# DZ_Scheme.net
KiCad netlist of a schematic drawn in Altium Designer
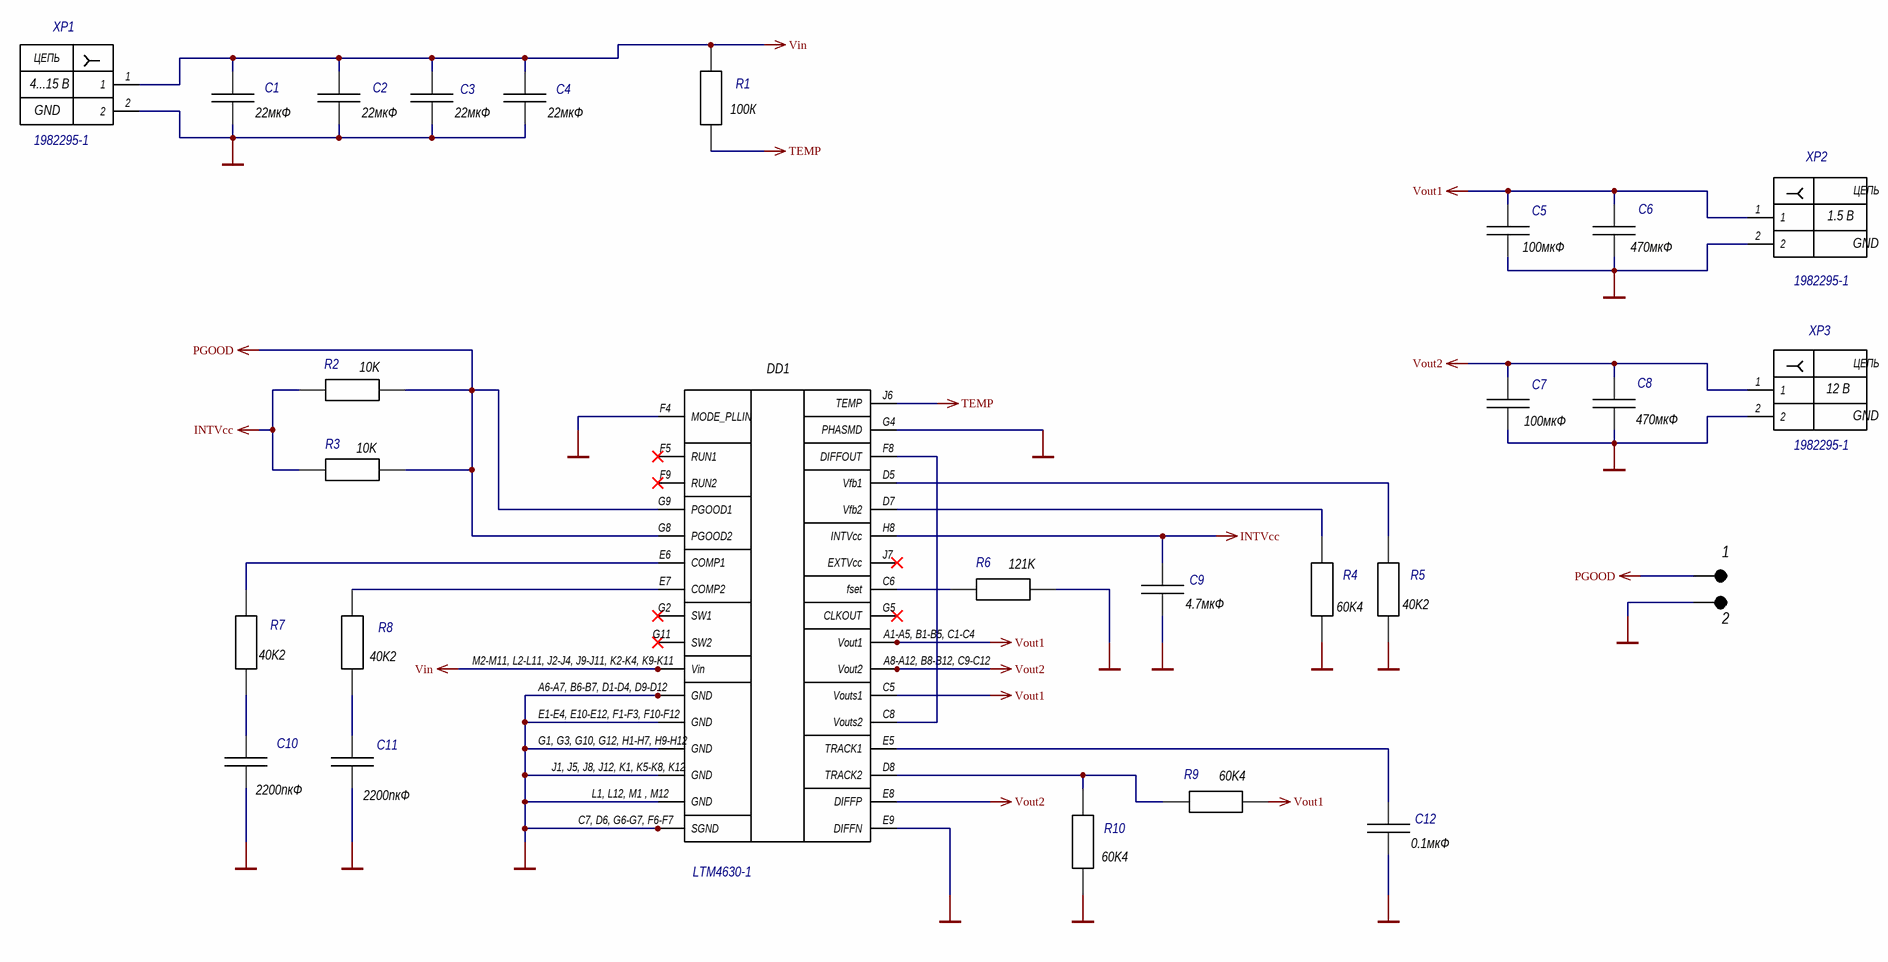
[diagram p0: DZ_Scheme.SchDoc]

(export (version "E")
  (design (tool "Eeschema 10.0.6"))
  (components
    (comp (ref "*")
      (value "TEST_PINS")
      (footprint "TEST_ZONE")
      (libsource (lib "DZ_Schlib") (part "TEST_PINS"))
    )
    (comp (ref "C1")
      (value "Capasitor")
      (footprint "CAP: 0805")
      (fields
        (field (name "PARAMETER 1") "22мкФ")
        (field (name "MANUFACTURER_PART_NUMBER") "CC0805MKX5R8BB226")
      )
      (libsource (lib "DZ_Schlib") (part "Capasitor"))
    )
    (comp (ref "C2")
      (value "Capasitor")
      (footprint "CAP: 0805")
      (fields
        (field (name "PARAMETER 1") "22мкФ")
        (field (name "MANUFACTURER_PART_NUMBER") "CC0805MKX5R8BB226")
      )
      (libsource (lib "DZ_Schlib") (part "Capasitor"))
    )
    (comp (ref "C3")
      (value "Capasitor")
      (footprint "CAP: 0805")
      (fields
        (field (name "PARAMETER 1") "22мкФ")
        (field (name "MANUFACTURER_PART_NUMBER") "CC0805MKX5R8BB226")
      )
      (libsource (lib "DZ_Schlib") (part "Capasitor"))
    )
    (comp (ref "C4")
      (value "Capasitor")
      (footprint "CAP: 0805")
      (fields
        (field (name "PARAMETER 1") "22мкФ")
        (field (name "MANUFACTURER_PART_NUMBER") "CC0805MKX5R8BB226")
      )
      (libsource (lib "DZ_Schlib") (part "Capasitor"))
    )
    (comp (ref "C5")
      (value "Capasitor")
      (footprint "CAP: 0805")
      (fields
        (field (name "PARAMETER 1") "100мкФ")
        (field (name "MANUFACTURER_PART_NUMBER") "GRM21BR60J107ME15")
      )
      (libsource (lib "DZ_Schlib") (part "Capasitor"))
    )
    (comp (ref "C6")
      (value "Capasitor")
      (footprint "CAP: 0805")
      (fields
        (field (name "PARAMETER 1") "470мкФ")
        (field (name "MANUFACTURER_PART_NUMBER") "CC0805KKX7R7BB474")
      )
      (libsource (lib "DZ_Schlib") (part "Capasitor"))
    )
    (comp (ref "C7")
      (value "Capasitor")
      (footprint "CAP: 0805")
      (fields
        (field (name "PARAMETER 1") "100мкФ")
        (field (name "MANUFACTURER_PART_NUMBER") "GRM21BR60J107ME15")
      )
      (libsource (lib "DZ_Schlib") (part "Capasitor"))
    )
    (comp (ref "C8")
      (value "Capasitor")
      (footprint "CAP: 0805")
      (fields
        (field (name "PARAMETER 1") "470мкФ")
        (field (name "MANUFACTURER_PART_NUMBER") "CC0805KKX7R7BB474")
      )
      (libsource (lib "DZ_Schlib") (part "Capasitor"))
    )
    (comp (ref "C9")
      (value "Capasitor")
      (footprint "CAP: 0805")
      (fields
        (field (name "PARAMETER 1") "4.7мкФ")
        (field (name "MANUFACTURER_PART_NUMBER") "CC0805KKX5R8BB475")
      )
      (libsource (lib "DZ_Schlib") (part "Capasitor"))
    )
    (comp (ref "C10")
      (value "Capasitor")
      (footprint "CAP: 0805")
      (fields
        (field (name "PARAMETER 1") "2200пкФ")
        (field (name "MANUFACTURER_PART_NUMBER") "CC0805JKNPO9BN222")
      )
      (libsource (lib "DZ_Schlib") (part "Capasitor"))
    )
    (comp (ref "C11")
      (value "Capasitor")
      (footprint "CAP: 0805")
      (fields
        (field (name "PARAMETER 1") "2200пкФ")
        (field (name "MANUFACTURER_PART_NUMBER") "CC0805JKNPO9BN222")
      )
      (libsource (lib "DZ_Schlib") (part "Capasitor"))
    )
    (comp (ref "C12")
      (value "Capasitor")
      (footprint "CAP: 0805")
      (fields
        (field (name "PARAMETER 1") "0.1мкФ")
        (field (name "MANUFACTURER_PART_NUMBER") "CC0805JRX7R8BB104")
      )
      (libsource (lib "DZ_Schlib") (part "Capasitor"))
    )
    (comp (ref "DD1")
      (value "LTM4630-1")
      (footprint "BGA144C127P12X12_1600X1600X501")
      (libsource (lib "DZ_Schlib") (part "LTM4630-1"))
    )
    (comp (ref "R1")
      (value "Resistor")
      (footprint "RES: 1206")
      (fields
        (field (name "PARAMETER 1") "100К")
        (field (name "MANUFACTURER_PART_NUMBER") "CRCW1206100KFKEA")
      )
      (libsource (lib "DZ_Schlib") (part "Resistor"))
    )
    (comp (ref "R2")
      (value "Resistor")
      (footprint "RES: 1206")
      (fields (field (name "PARAMETER 1") "10K") (field (name "MANUFACTURER_PART_NUMBER") "CRCW120610K0FKEA"))
      (libsource (lib "DZ_Schlib") (part "Resistor"))
    )
    (comp (ref "R3")
      (value "Resistor")
      (footprint "RES: 1206")
      (fields (field (name "PARAMETER 1") "10K") (field (name "MANUFACTURER_PART_NUMBER") "CRCW120610K0FKEA"))
      (libsource (lib "DZ_Schlib") (part "Resistor"))
    )
    (comp (ref "R4")
      (value "Resistor")
      (footprint "RES: 1206")
      (fields
        (field (name "PARAMETER 1") "60K4")
        (field (name "MANUFACTURER_PART_NUMBER") "CRCW120660K4FKEA")
      )
      (libsource (lib "DZ_Schlib") (part "Resistor"))
    )
    (comp (ref "R5")
      (value "Resistor")
      (footprint "RES: 1206")
      (fields
        (field (name "PARAMETER 1") "40K2")
        (field (name "MANUFACTURER_PART_NUMBER") "CRCW120640K2FHEAP")
      )
      (libsource (lib "DZ_Schlib") (part "Resistor"))
    )
    (comp (ref "R6")
      (value "Resistor")
      (footprint "RES: 1206")
      (fields
        (field (name "PARAMETER 1") "121K")
        (field (name "MANUFACTURER_PART_NUMBER") "CRCW1206121KFHEAP")
      )
      (libsource (lib "DZ_Schlib") (part "Resistor"))
    )
    (comp (ref "R7")
      (value "Resistor")
      (footprint "RES: 1206")
      (fields
        (field (name "PARAMETER 1") "40K2")
        (field (name "MANUFACTURER_PART_NUMBER") "CRCW120640K2FHEAP")
      )
      (libsource (lib "DZ_Schlib") (part "Resistor"))
    )
    (comp (ref "R8")
      (value "Resistor")
      (footprint "RES: 1206")
      (fields
        (field (name "PARAMETER 1") "40K2")
        (field (name "MANUFACTURER_PART_NUMBER") "CRCW120640K2FHEAP")
      )
      (libsource (lib "DZ_Schlib") (part "Resistor"))
    )
    (comp (ref "R9")
      (value "Resistor")
      (footprint "RES: 1206")
      (fields
        (field (name "PARAMETER 1") "60K4")
        (field (name "MANUFACTURER_PART_NUMBER") "CRCW120660K4FKEA")
      )
      (libsource (lib "DZ_Schlib") (part "Resistor"))
    )
    (comp (ref "R10")
      (value "Resistor")
      (footprint "RES: 1206")
      (fields
        (field (name "PARAMETER 1") "60K4")
        (field (name "MANUFACTURER_PART_NUMBER") "CRCW120660K4FKEA")
      )
      (libsource (lib "DZ_Schlib") (part "Resistor"))
    )
    (comp (ref "XP1")
      (value "1982295-1")
      (footprint "DZ_PcbLib:19822951")
      (description "Connector")
      (fields (field (name "MOUSER PART NUMBER") "571-1982295-1"))
      (libsource (lib "") (part "1982295-1_1"))
    )
    (comp (ref "XP2")
      (value "1982295-1")
      (footprint "DZ_PcbLib:19822951")
      (description "Connector")
      (fields (field (name "MOUSER PART NUMBER") "571-1982295-1"))
      (libsource (lib "DZ_Schlib") (part "1982295-1"))
    )
    (comp (ref "XP3")
      (value "1982295-1")
      (footprint "DZ_PcbLib:19822951")
      (description "Connector")
      (fields (field (name "MOUSER PART NUMBER") "571-1982295-1"))
      (libsource (lib "DZ_Schlib") (part "1982295-1"))
    )
  )
  (nets
    (net (code "1") (name "GND") (class "Default")
      (node (ref "*") (pin "2") (pinfunction "2_2") (pintype "passive"))
      (node (ref "C1") (pin "1") (pinfunction "1_1") (pintype "passive"))
      (node (ref "C10") (pin "1") (pinfunction "1_1") (pintype "passive"))
      (node (ref "C11") (pin "2") (pinfunction "2_2") (pintype "passive"))
      (node (ref "C12") (pin "1") (pinfunction "1_1") (pintype "passive"))
      (node (ref "C2") (pin "1") (pinfunction "1_1") (pintype "passive"))
      (node (ref "C3") (pin "1") (pinfunction "1_1") (pintype "passive"))
      (node (ref "C4") (pin "1") (pinfunction "1_1") (pintype "passive"))
      (node (ref "C5") (pin "1") (pinfunction "1_1") (pintype "passive"))
      (node (ref "C6") (pin "2") (pinfunction "2_2") (pintype "passive"))
      (node (ref "C7") (pin "1") (pinfunction "1_1") (pintype "passive"))
      (node (ref "C8") (pin "2") (pinfunction "2_2") (pintype "passive"))
      (node (ref "C9") (pin "1") (pinfunction "1_1") (pintype "passive"))
      (node (ref "DD1") (pin "A6") (pinfunction "GND_A6") (pintype "open_emitter"))
      (node (ref "DD1") (pin "A7") (pinfunction "GND_A7") (pintype "open_emitter"))
      (node (ref "DD1") (pin "B6") (pinfunction "GND_B6") (pintype "open_emitter"))
      (node (ref "DD1") (pin "B7") (pinfunction "GND_B7") (pintype "open_emitter"))
      (node (ref "DD1") (pin "C7") (pinfunction "SGND_C7") (pintype "open_emitter"))
      (node (ref "DD1") (pin "D1") (pinfunction "GND_D1") (pintype "open_emitter"))
      (node (ref "DD1") (pin "D10") (pinfunction "GND_D10") (pintype "open_emitter"))
      (node (ref "DD1") (pin "D11") (pinfunction "GND_D11") (pintype "open_emitter"))
      (node (ref "DD1") (pin "D12") (pinfunction "GND_D12") (pintype "open_emitter"))
      (node (ref "DD1") (pin "D2") (pinfunction "GND_D2") (pintype "open_emitter"))
      (node (ref "DD1") (pin "D3") (pinfunction "GND_D3") (pintype "open_emitter"))
      (node (ref "DD1") (pin "D4") (pinfunction "GND_D4") (pintype "open_emitter"))
      (node (ref "DD1") (pin "D6") (pinfunction "SGND_D6") (pintype "open_emitter"))
      (node (ref "DD1") (pin "D9") (pinfunction "GND_D9") (pintype "open_emitter"))
      (node (ref "DD1") (pin "E1") (pinfunction "GND_E1") (pintype "open_emitter"))
      (node (ref "DD1") (pin "E10") (pinfunction "GND_E10") (pintype "open_emitter"))
      (node (ref "DD1") (pin "E11") (pinfunction "GND_E11") (pintype "open_emitter"))
      (node (ref "DD1") (pin "E12") (pinfunction "GND_E12") (pintype "open_emitter"))
      (node (ref "DD1") (pin "E2") (pinfunction "GND_E2") (pintype "open_emitter"))
      (node (ref "DD1") (pin "E3") (pinfunction "GND_E3") (pintype "open_emitter"))
      (node (ref "DD1") (pin "E4") (pinfunction "GND_E4") (pintype "open_emitter"))
      (node (ref "DD1") (pin "E9") (pinfunction "DIFFN_E9") (pintype "open_emitter"))
      (node (ref "DD1") (pin "F1") (pinfunction "GND_F1") (pintype "open_emitter"))
      (node (ref "DD1") (pin "F10") (pinfunction "GND_F10") (pintype "open_emitter"))
      (node (ref "DD1") (pin "F11") (pinfunction "GND_F11") (pintype "open_emitter"))
      (node (ref "DD1") (pin "F12") (pinfunction "GND_F12") (pintype "open_emitter"))
      (node (ref "DD1") (pin "F2") (pinfunction "GND_F2") (pintype "open_emitter"))
      (node (ref "DD1") (pin "F3") (pinfunction "GND_F3") (pintype "open_emitter"))
      (node (ref "DD1") (pin "F4") (pinfunction "MODE_PLLIN_F4") (pintype "open_emitter"))
      (node (ref "DD1") (pin "F6") (pinfunction "SGND_F6") (pintype "open_emitter"))
      (node (ref "DD1") (pin "F7") (pinfunction "SGND_F7") (pintype "open_emitter"))
      (node (ref "DD1") (pin "G1") (pinfunction "GND_G1") (pintype "open_emitter"))
      (node (ref "DD1") (pin "G10") (pinfunction "GND_G10") (pintype "open_emitter"))
      (node (ref "DD1") (pin "G12") (pinfunction "GND_G12") (pintype "open_emitter"))
      (node (ref "DD1") (pin "G3") (pinfunction "GND_G3") (pintype "open_emitter"))
      (node (ref "DD1") (pin "G4") (pinfunction "PHASMD_G4") (pintype "open_emitter"))
      (node (ref "DD1") (pin "G6") (pinfunction "SGND_G6") (pintype "open_emitter"))
      (node (ref "DD1") (pin "G7") (pinfunction "SGND_G7") (pintype "open_emitter"))
      (node (ref "DD1") (pin "H1") (pinfunction "GND_H1") (pintype "open_emitter"))
      (node (ref "DD1") (pin "H10") (pinfunction "GND_H10") (pintype "open_emitter"))
      (node (ref "DD1") (pin "H11") (pinfunction "GND_H11") (pintype "open_emitter"))
      (node (ref "DD1") (pin "H12") (pinfunction "GND_H12") (pintype "open_emitter"))
      (node (ref "DD1") (pin "H2") (pinfunction "GND_H2") (pintype "open_emitter"))
      (node (ref "DD1") (pin "H3") (pinfunction "GND_H3") (pintype "open_emitter"))
      (node (ref "DD1") (pin "H4") (pinfunction "GND_H4") (pintype "open_emitter"))
      (node (ref "DD1") (pin "H5") (pinfunction "GND_H5") (pintype "open_emitter"))
      (node (ref "DD1") (pin "H6") (pinfunction "GND_H6") (pintype "open_emitter"))
      (node (ref "DD1") (pin "H7") (pinfunction "GND_H7") (pintype "open_emitter"))
      (node (ref "DD1") (pin "H9") (pinfunction "GND_H9") (pintype "open_emitter"))
      (node (ref "DD1") (pin "J1") (pinfunction "GND_J1") (pintype "open_emitter"))
      (node (ref "DD1") (pin "J12") (pinfunction "GND_J12") (pintype "open_emitter"))
      (node (ref "DD1") (pin "J5") (pinfunction "GND_J5") (pintype "open_emitter"))
      (node (ref "DD1") (pin "J8") (pinfunction "GND_J8") (pintype "open_emitter"))
      (node (ref "DD1") (pin "K1") (pinfunction "GND_K1") (pintype "open_emitter"))
      (node (ref "DD1") (pin "K12") (pinfunction "GND_K12") (pintype "open_emitter"))
      (node (ref "DD1") (pin "K5") (pinfunction "GND_K5") (pintype "open_emitter"))
      (node (ref "DD1") (pin "K6") (pinfunction "GND_K6") (pintype "open_emitter"))
      (node (ref "DD1") (pin "K7") (pinfunction "GND_K7") (pintype "open_emitter"))
      (node (ref "DD1") (pin "K8") (pinfunction "GND_K8") (pintype "open_emitter"))
      (node (ref "DD1") (pin "L1") (pinfunction "GND_L1") (pintype "open_emitter"))
      (node (ref "DD1") (pin "L12") (pinfunction "GND_L12") (pintype "open_emitter"))
      (node (ref "DD1") (pin "M1") (pinfunction "GND_M1") (pintype "open_emitter"))
      (node (ref "DD1") (pin "M12") (pinfunction "GND_M12") (pintype "open_emitter"))
      (node (ref "R10") (pin "1") (pinfunction "1_1") (pintype "passive"))
      (node (ref "R4") (pin "1") (pinfunction "1_1") (pintype "passive"))
      (node (ref "R5") (pin "1") (pinfunction "1_1") (pintype "passive"))
      (node (ref "R6") (pin "2") (pinfunction "2_2") (pintype "passive"))
      (node (ref "XP1") (pin "2") (pinfunction "2_2") (pintype "open_emitter"))
      (node (ref "XP2") (pin "2") (pinfunction "2_2") (pintype "open_emitter"))
      (node (ref "XP3") (pin "2") (pinfunction "2_2") (pintype "open_emitter"))
    )
    (net (code "2") (name "INTVcc") (class "Default")
      (node (ref "C9") (pin "2") (pinfunction "2_2") (pintype "passive"))
      (node (ref "DD1") (pin "H8") (pinfunction "INTVcc_H8") (pintype "open_emitter"))
      (node (ref "R2") (pin "1") (pinfunction "1_1") (pintype "passive"))
      (node (ref "R3") (pin "1") (pinfunction "1_1") (pintype "passive"))
    )
    (net (code "3") (name "Net-(C10-Pad2)") (class "Default")
      (node (ref "C10") (pin "2") (pinfunction "2_2") (pintype "passive"))
      (node (ref "R7") (pin "2") (pinfunction "2_2") (pintype "passive"))
    )
    (net (code "4") (name "Net-(C11-Pad1)") (class "Default")
      (node (ref "C11") (pin "1") (pinfunction "1_1") (pintype "passive"))
      (node (ref "R8") (pin "2") (pinfunction "2_2") (pintype "passive"))
    )
    (net (code "5") (name "Net-(DD1-COMP1)") (class "Default")
      (node (ref "DD1") (pin "E6") (pinfunction "COMP1_E6") (pintype "open_emitter"))
      (node (ref "R7") (pin "1") (pinfunction "1_1") (pintype "passive"))
    )
    (net (code "6") (name "Net-(DD1-COMP2)") (class "Default")
      (node (ref "DD1") (pin "E7") (pinfunction "COMP2_E7") (pintype "open_emitter"))
      (node (ref "R8") (pin "1") (pinfunction "1_1") (pintype "passive"))
    )
    (net (code "7") (name "Net-(DD1-DIFFOUT)") (class "Default")
      (node (ref "DD1") (pin "C8") (pinfunction "Vouts2_C8") (pintype "open_emitter"))
      (node (ref "DD1") (pin "F8") (pinfunction "DIFFOUT_F8") (pintype "open_emitter"))
    )
    (net (code "8") (name "Net-(DD1-TRACK1)") (class "Default")
      (node (ref "C12") (pin "2") (pinfunction "2_2") (pintype "passive"))
      (node (ref "DD1") (pin "E5") (pinfunction "TRACK1_E5") (pintype "open_emitter"))
    )
    (net (code "9") (name "Net-(DD1-TRACK2)") (class "Default")
      (node (ref "DD1") (pin "D8") (pinfunction "TRACK2_D8") (pintype "open_emitter"))
      (node (ref "R10") (pin "2") (pinfunction "2_2") (pintype "passive"))
      (node (ref "R9") (pin "2") (pinfunction "2_2") (pintype "passive"))
    )
    (net (code "10") (name "Net-(DD1-Vfb1)") (class "Default")
      (node (ref "DD1") (pin "D5") (pinfunction "Vfb1_D5") (pintype "open_emitter"))
      (node (ref "R5") (pin "2") (pinfunction "2_2") (pintype "passive"))
    )
    (net (code "11") (name "Net-(DD1-Vfb2)") (class "Default")
      (node (ref "DD1") (pin "D7") (pinfunction "Vfb2_D7") (pintype "open_emitter"))
      (node (ref "R4") (pin "2") (pinfunction "2_2") (pintype "passive"))
    )
    (net (code "12") (name "Net-(DD1-fset)") (class "Default")
      (node (ref "DD1") (pin "C6") (pinfunction "fset_C6") (pintype "open_emitter"))
      (node (ref "R6") (pin "1") (pinfunction "1_1") (pintype "passive"))
    )
    (net (code "13") (name "PGOOD") (class "Default")
      (node (ref "*") (pin "1") (pinfunction "1_1") (pintype "passive"))
      (node (ref "DD1") (pin "G8") (pinfunction "PGOOD2_G8") (pintype "open_emitter"))
      (node (ref "DD1") (pin "G9") (pinfunction "PGOOD1_G9") (pintype "open_emitter"))
      (node (ref "R2") (pin "2") (pinfunction "2_2") (pintype "passive"))
      (node (ref "R3") (pin "2") (pinfunction "2_2") (pintype "passive"))
    )
    (net (code "14") (name "TEMP") (class "Default")
      (node (ref "DD1") (pin "J6") (pinfunction "TEMP_J6") (pintype "open_emitter"))
      (node (ref "R1") (pin "1") (pinfunction "1_1") (pintype "passive"))
    )
    (net (code "15") (name "Vin") (class "Default")
      (node (ref "C1") (pin "2") (pinfunction "2_2") (pintype "passive"))
      (node (ref "C2") (pin "2") (pinfunction "2_2") (pintype "passive"))
      (node (ref "C3") (pin "2") (pinfunction "2_2") (pintype "passive"))
      (node (ref "C4") (pin "2") (pinfunction "2_2") (pintype "passive"))
      (node (ref "DD1") (pin "J10") (pinfunction "Vin_J10") (pintype "open_emitter"))
      (node (ref "DD1") (pin "J11") (pinfunction "Vin_J11") (pintype "open_emitter"))
      (node (ref "DD1") (pin "J2") (pinfunction "Vin_J2") (pintype "open_emitter"))
      (node (ref "DD1") (pin "J3") (pinfunction "Vin_J3") (pintype "open_emitter"))
      (node (ref "DD1") (pin "J4") (pinfunction "Vin_J4") (pintype "open_emitter"))
      (node (ref "DD1") (pin "J9") (pinfunction "Vin_J9") (pintype "open_emitter"))
      (node (ref "DD1") (pin "K10") (pinfunction "Vin_K10") (pintype "open_emitter"))
      (node (ref "DD1") (pin "K11") (pinfunction "Vin_K11") (pintype "open_emitter"))
      (node (ref "DD1") (pin "K2") (pinfunction "Vin_K2") (pintype "open_emitter"))
      (node (ref "DD1") (pin "K3") (pinfunction "Vin_K3") (pintype "open_emitter"))
      (node (ref "DD1") (pin "K4") (pinfunction "Vin_K4") (pintype "open_emitter"))
      (node (ref "DD1") (pin "K9") (pinfunction "Vin_K9") (pintype "open_emitter"))
      (node (ref "DD1") (pin "L10") (pinfunction "Vin_L10") (pintype "open_emitter"))
      (node (ref "DD1") (pin "L11") (pinfunction "Vin_L11") (pintype "open_emitter"))
      (node (ref "DD1") (pin "L2") (pinfunction "Vin_L2") (pintype "open_emitter"))
      (node (ref "DD1") (pin "L3") (pinfunction "Vin_L3") (pintype "open_emitter"))
      (node (ref "DD1") (pin "L4") (pinfunction "Vin_L4") (pintype "open_emitter"))
      (node (ref "DD1") (pin "L5") (pinfunction "Vin_L5") (pintype "open_emitter"))
      (node (ref "DD1") (pin "L6") (pinfunction "Vin_L6") (pintype "open_emitter"))
      (node (ref "DD1") (pin "L7") (pinfunction "Vin_L7") (pintype "open_emitter"))
      (node (ref "DD1") (pin "L8") (pinfunction "Vin_L8") (pintype "open_emitter"))
      (node (ref "DD1") (pin "L9") (pinfunction "Vin_L9") (pintype "open_emitter"))
      (node (ref "DD1") (pin "M10") (pinfunction "Vin_M10") (pintype "open_emitter"))
      (node (ref "DD1") (pin "M11") (pinfunction "Vin_M11") (pintype "open_emitter"))
      (node (ref "DD1") (pin "M2") (pinfunction "Vin_M2") (pintype "open_emitter"))
      (node (ref "DD1") (pin "M3") (pinfunction "Vin_M3") (pintype "open_emitter"))
      (node (ref "DD1") (pin "M4") (pinfunction "Vin_M4") (pintype "open_emitter"))
      (node (ref "DD1") (pin "M5") (pinfunction "Vin_M5") (pintype "open_emitter"))
      (node (ref "DD1") (pin "M6") (pinfunction "Vin_M6") (pintype "open_emitter"))
      (node (ref "DD1") (pin "M7") (pinfunction "Vin_M7") (pintype "open_emitter"))
      (node (ref "DD1") (pin "M8") (pinfunction "Vin_M8") (pintype "open_emitter"))
      (node (ref "DD1") (pin "M9") (pinfunction "Vin_M9") (pintype "open_emitter"))
      (node (ref "R1") (pin "2") (pinfunction "2_2") (pintype "passive"))
      (node (ref "XP1") (pin "1") (pinfunction "1_1") (pintype "passive"))
    )
    (net (code "16") (name "Vout1") (class "Default")
      (node (ref "C5") (pin "2") (pinfunction "2_2") (pintype "passive"))
      (node (ref "C6") (pin "1") (pinfunction "1_1") (pintype "passive"))
      (node (ref "DD1") (pin "A1") (pinfunction "Vout1_A1") (pintype "open_emitter"))
      (node (ref "DD1") (pin "A2") (pinfunction "Vout1_A2") (pintype "open_emitter"))
      (node (ref "DD1") (pin "A3") (pinfunction "Vout1_A3") (pintype "open_emitter"))
      (node (ref "DD1") (pin "A4") (pinfunction "Vout1_A4") (pintype "open_emitter"))
      (node (ref "DD1") (pin "A5") (pinfunction "Vout1_A5") (pintype "open_emitter"))
      (node (ref "DD1") (pin "B1") (pinfunction "Vout1_B1") (pintype "open_emitter"))
      (node (ref "DD1") (pin "B2") (pinfunction "Vout1_B2") (pintype "open_emitter"))
      (node (ref "DD1") (pin "B3") (pinfunction "Vout1_B3") (pintype "open_emitter"))
      (node (ref "DD1") (pin "B4") (pinfunction "Vout1_B4") (pintype "open_emitter"))
      (node (ref "DD1") (pin "B5") (pinfunction "Vout1_B5") (pintype "open_emitter"))
      (node (ref "DD1") (pin "C1") (pinfunction "Vout1_C1") (pintype "open_emitter"))
      (node (ref "DD1") (pin "C2") (pinfunction "Vout1_C2") (pintype "open_emitter"))
      (node (ref "DD1") (pin "C3") (pinfunction "Vout1_C3") (pintype "open_emitter"))
      (node (ref "DD1") (pin "C4") (pinfunction "Vout1_C4") (pintype "open_emitter"))
      (node (ref "DD1") (pin "C5") (pinfunction "Vouts1_C5") (pintype "open_emitter"))
      (node (ref "R9") (pin "1") (pinfunction "1_1") (pintype "passive"))
      (node (ref "XP2") (pin "1") (pinfunction "1_1") (pintype "passive"))
    )
    (net (code "17") (name "Vout2") (class "Default")
      (node (ref "C7") (pin "2") (pinfunction "2_2") (pintype "passive"))
      (node (ref "C8") (pin "1") (pinfunction "1_1") (pintype "passive"))
      (node (ref "DD1") (pin "A10") (pinfunction "Vout2_A10") (pintype "open_emitter"))
      (node (ref "DD1") (pin "A11") (pinfunction "Vout2_A11") (pintype "open_emitter"))
      (node (ref "DD1") (pin "A12") (pinfunction "Vout2_A12") (pintype "open_emitter"))
      (node (ref "DD1") (pin "A8") (pinfunction "Vout2_A8") (pintype "open_emitter"))
      (node (ref "DD1") (pin "A9") (pinfunction "Vout2_A9") (pintype "open_emitter"))
      (node (ref "DD1") (pin "B10") (pinfunction "Vout2_B10") (pintype "open_emitter"))
      (node (ref "DD1") (pin "B11") (pinfunction "Vout2_B11") (pintype "open_emitter"))
      (node (ref "DD1") (pin "B12") (pinfunction "Vout2_B12") (pintype "open_emitter"))
      (node (ref "DD1") (pin "B8") (pinfunction "Vout2_B8") (pintype "open_emitter"))
      (node (ref "DD1") (pin "B9") (pinfunction "Vout2_B9") (pintype "open_emitter"))
      (node (ref "DD1") (pin "C10") (pinfunction "Vout2_C10") (pintype "open_emitter"))
      (node (ref "DD1") (pin "C11") (pinfunction "Vout2_C11") (pintype "open_emitter"))
      (node (ref "DD1") (pin "C12") (pinfunction "Vout2_C12") (pintype "open_emitter"))
      (node (ref "DD1") (pin "C9") (pinfunction "Vout2_C9") (pintype "open_emitter"))
      (node (ref "DD1") (pin "E8") (pinfunction "DIFFP_E8") (pintype "open_emitter"))
      (node (ref "XP3") (pin "1") (pinfunction "1_1") (pintype "passive"))
    )
    (net (code "18") (name "unconnected-(DD1-CLKOUT-PadG5)") (class "Default")
      (node (ref "DD1") (pin "G5") (pinfunction "CLKOUT_G5") (pintype "open_emitter+no_connect"))
    )
    (net (code "19") (name "unconnected-(DD1-EXTVcc-PadJ7)") (class "Default")
      (node (ref "DD1") (pin "J7") (pinfunction "EXTVcc_J7") (pintype "open_emitter+no_connect"))
    )
    (net (code "20") (name "unconnected-(DD1-RUN1-PadF5)") (class "Default")
      (node (ref "DD1") (pin "F5") (pinfunction "RUN1_F5") (pintype "open_emitter+no_connect"))
    )
    (net (code "21") (name "unconnected-(DD1-RUN2-PadF9)") (class "Default")
      (node (ref "DD1") (pin "F9") (pinfunction "RUN2_F9") (pintype "open_emitter+no_connect"))
    )
    (net (code "22") (name "unconnected-(DD1-SW1-PadG2)") (class "Default")
      (node (ref "DD1") (pin "G2") (pinfunction "SW1_G2") (pintype "open_emitter+no_connect"))
    )
    (net (code "23") (name "unconnected-(DD1-SW2-PadG11)") (class "Default")
      (node (ref "DD1") (pin "G11") (pinfunction "SW2_G11") (pintype "open_emitter+no_connect"))
    )
  )
)
